# Taller_Arrancador_EAGLE_V1_0_0.net
KiCad netlist of a schematic drawn in EAGLE
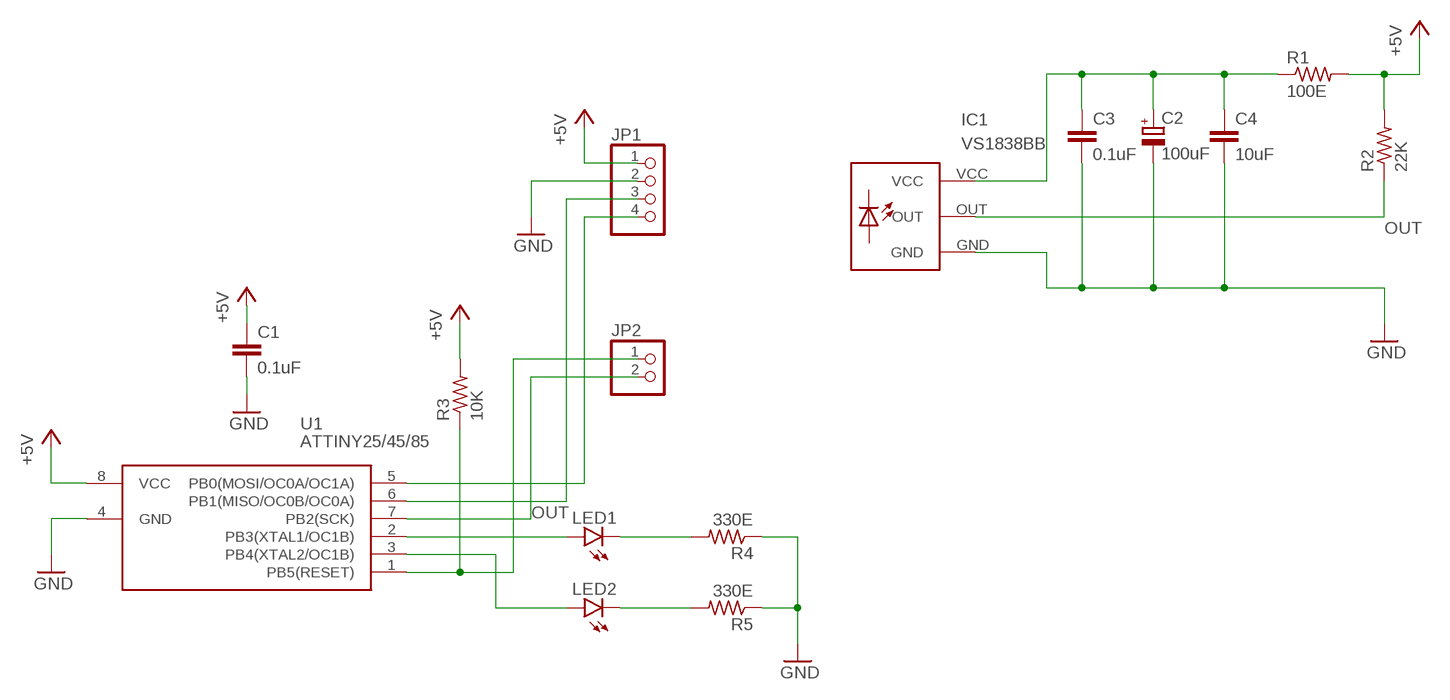
[diagram p0: schematic, sheet 1]

(export (version "E")
  (design (tool "Eeschema 10.0.6"))
  (components
    (comp (ref "C1")
      (value "0.1uF")
      (footprint "eagle-import:C0603")
      (libsource (lib "eagle-import") (part "C-EUC0603"))
    )
    (comp (ref "C2")
      (value "100uF")
      (footprint "eagle-import:CT3216")
      (libsource (lib "eagle-import") (part "CPOL-EUCT3216"))
    )
    (comp (ref "C3")
      (value "0.1uF")
      (footprint "eagle-import:C0603")
      (libsource (lib "eagle-import") (part "C-EUC0603"))
    )
    (comp (ref "C4")
      (value "10uF")
      (footprint "eagle-import:C0603")
      (libsource (lib "eagle-import") (part "C-EUC0603"))
    )
    (comp (ref "IC1")
      (value "VS1838BB")
      (footprint "eagle-import:VS1838B")
      (libsource (lib "eagle-import") (part "VS1838BB"))
    )
    (comp (ref "JP1")
      (value "PINHD-1X04_2.54-S")
      (footprint "eagle-import:1X04-S")
      (libsource (lib "eagle-import") (part "PINHD-1X04_2.54-S"))
    )
    (comp (ref "JP2")
      (value "PINHD-1X02_2.54-S")
      (footprint "eagle-import:1X02-S")
      (libsource (lib "eagle-import") (part "PINHD-1X02_2.54-S"))
    )
    (comp (ref "LED1")
      (value "LEDCHIP-LED0603")
      (footprint "eagle-import:CHIP-LED0603")
      (libsource (lib "eagle-import") (part "LEDCHIP-LED0603"))
    )
    (comp (ref "LED2")
      (value "LEDCHIP-LED0603")
      (footprint "eagle-import:CHIP-LED0603")
      (libsource (lib "eagle-import") (part "LEDCHIP-LED0603"))
    )
    (comp (ref "R1")
      (value "100E")
      (footprint "eagle-import:R0603")
      (libsource (lib "eagle-import") (part "R-US_R0603"))
    )
    (comp (ref "R2")
      (value "22K")
      (footprint "eagle-import:R0603")
      (libsource (lib "eagle-import") (part "R-US_R0603"))
    )
    (comp (ref "R3")
      (value "10K")
      (footprint "eagle-import:R0603")
      (libsource (lib "eagle-import") (part "R-US_R0603"))
    )
    (comp (ref "R4")
      (value "330E")
      (footprint "eagle-import:R0603")
      (libsource (lib "eagle-import") (part "R-US_R0603"))
    )
    (comp (ref "R5")
      (value "330E")
      (footprint "eagle-import:R0603")
      (libsource (lib "eagle-import") (part "R-US_R0603"))
    )
    (comp (ref "U1")
      (value "ATTINY25/45/85")
      (footprint "eagle-import:TSSOP-8")
      (libsource (lib "eagle-import") (part "ATTINY25/45/85"))
    )
  )
  (nets
    (net (code "1") (name "+5V") (class "Default")
      (node (ref "C1") (pin "1") (pinfunction "1_1") (pintype "passive"))
      (node (ref "JP1") (pin "1") (pinfunction "1_1") (pintype "passive"))
      (node (ref "R1") (pin "2") (pinfunction "2_2") (pintype "passive"))
      (node (ref "R2") (pin "2") (pinfunction "2_2") (pintype "passive"))
      (node (ref "R3") (pin "2") (pinfunction "2_2") (pintype "passive"))
      (node (ref "U1") (pin "8") (pinfunction "VCC_8") (pintype "power_in"))
    )
    (net (code "2") (name "/OUT") (class "Default")
      (node (ref "IC1") (pin "OUT") (pinfunction "OUT_OUT") (pintype "output"))
      (node (ref "JP2") (pin "2") (pinfunction "2_2") (pintype "passive"))
      (node (ref "R2") (pin "1") (pinfunction "1_1") (pintype "passive"))
      (node (ref "U1") (pin "7") (pinfunction "PB2(SCK)_7") (pintype "bidirectional"))
    )
    (net (code "3") (name "GND") (class "Default")
      (node (ref "C1") (pin "2") (pinfunction "2_2") (pintype "passive"))
      (node (ref "C2") (pin "-") (pinfunction "-_-") (pintype "passive"))
      (node (ref "C3") (pin "2") (pinfunction "2_2") (pintype "passive"))
      (node (ref "C4") (pin "2") (pinfunction "2_2") (pintype "passive"))
      (node (ref "IC1") (pin "GND") (pinfunction "GND_GND") (pintype "power_in"))
      (node (ref "JP1") (pin "2") (pinfunction "2_2") (pintype "passive"))
      (node (ref "R4") (pin "1") (pinfunction "1_1") (pintype "passive"))
      (node (ref "R5") (pin "1") (pinfunction "1_1") (pintype "passive"))
      (node (ref "U1") (pin "4") (pinfunction "GND_4") (pintype "power_in"))
    )
    (net (code "4") (name "Net-(C2-Pad+)") (class "Default")
      (node (ref "C2") (pin "+") (pinfunction "+_+") (pintype "passive"))
      (node (ref "C3") (pin "1") (pinfunction "1_1") (pintype "passive"))
      (node (ref "C4") (pin "1") (pinfunction "1_1") (pintype "passive"))
      (node (ref "IC1") (pin "VCC") (pinfunction "VCC_VCC") (pintype "power_in"))
      (node (ref "R1") (pin "1") (pinfunction "1_1") (pintype "passive"))
    )
    (net (code "5") (name "Net-(LED1-PadC)") (class "Default")
      (node (ref "LED1") (pin "C") (pinfunction "C_C") (pintype "passive"))
      (node (ref "R4") (pin "2") (pinfunction "2_2") (pintype "passive"))
    )
    (net (code "6") (name "Net-(LED2-PadC)") (class "Default")
      (node (ref "LED2") (pin "C") (pinfunction "C_C") (pintype "passive"))
      (node (ref "R5") (pin "2") (pinfunction "2_2") (pintype "passive"))
    )
    (net (code "7") (name "Net-(U1-PB0(MOSI{slash}OC0A{slash}OC1A))") (class "Default")
      (node (ref "JP1") (pin "4") (pinfunction "4_4") (pintype "passive"))
      (node (ref "U1") (pin "5") (pinfunction "PB0(MOSI/OC0A/OC1A)_5") (pintype "bidirectional"))
    )
    (net (code "8") (name "Net-(U1-PB1(MISO{slash}OC0B{slash}OC0A))") (class "Default")
      (node (ref "JP1") (pin "3") (pinfunction "3_3") (pintype "passive"))
      (node (ref "U1") (pin "6") (pinfunction "PB1(MISO/OC0B/OC0A)_6") (pintype "bidirectional"))
    )
    (net (code "9") (name "Net-(U1-PB3(XTAL1{slash}OC1B))") (class "Default")
      (node (ref "LED1") (pin "A") (pinfunction "A_A") (pintype "passive"))
      (node (ref "U1") (pin "2") (pinfunction "PB3(XTAL1/OC1B)_2") (pintype "bidirectional"))
    )
    (net (code "10") (name "Net-(U1-PB4(XTAL2{slash}OC1B))") (class "Default")
      (node (ref "LED2") (pin "A") (pinfunction "A_A") (pintype "passive"))
      (node (ref "U1") (pin "3") (pinfunction "PB4(XTAL2/OC1B)_3") (pintype "bidirectional"))
    )
    (net (code "11") (name "Net-(U1-PB5(RESET))") (class "Default")
      (node (ref "JP2") (pin "1") (pinfunction "1_1") (pintype "passive"))
      (node (ref "R3") (pin "1") (pinfunction "1_1") (pintype "passive"))
      (node (ref "U1") (pin "1") (pinfunction "PB5(RESET)_1") (pintype "bidirectional"))
    )
  )
)
